# 02_connector.net
KiCad netlist of a schematic drawn in Altium Designer
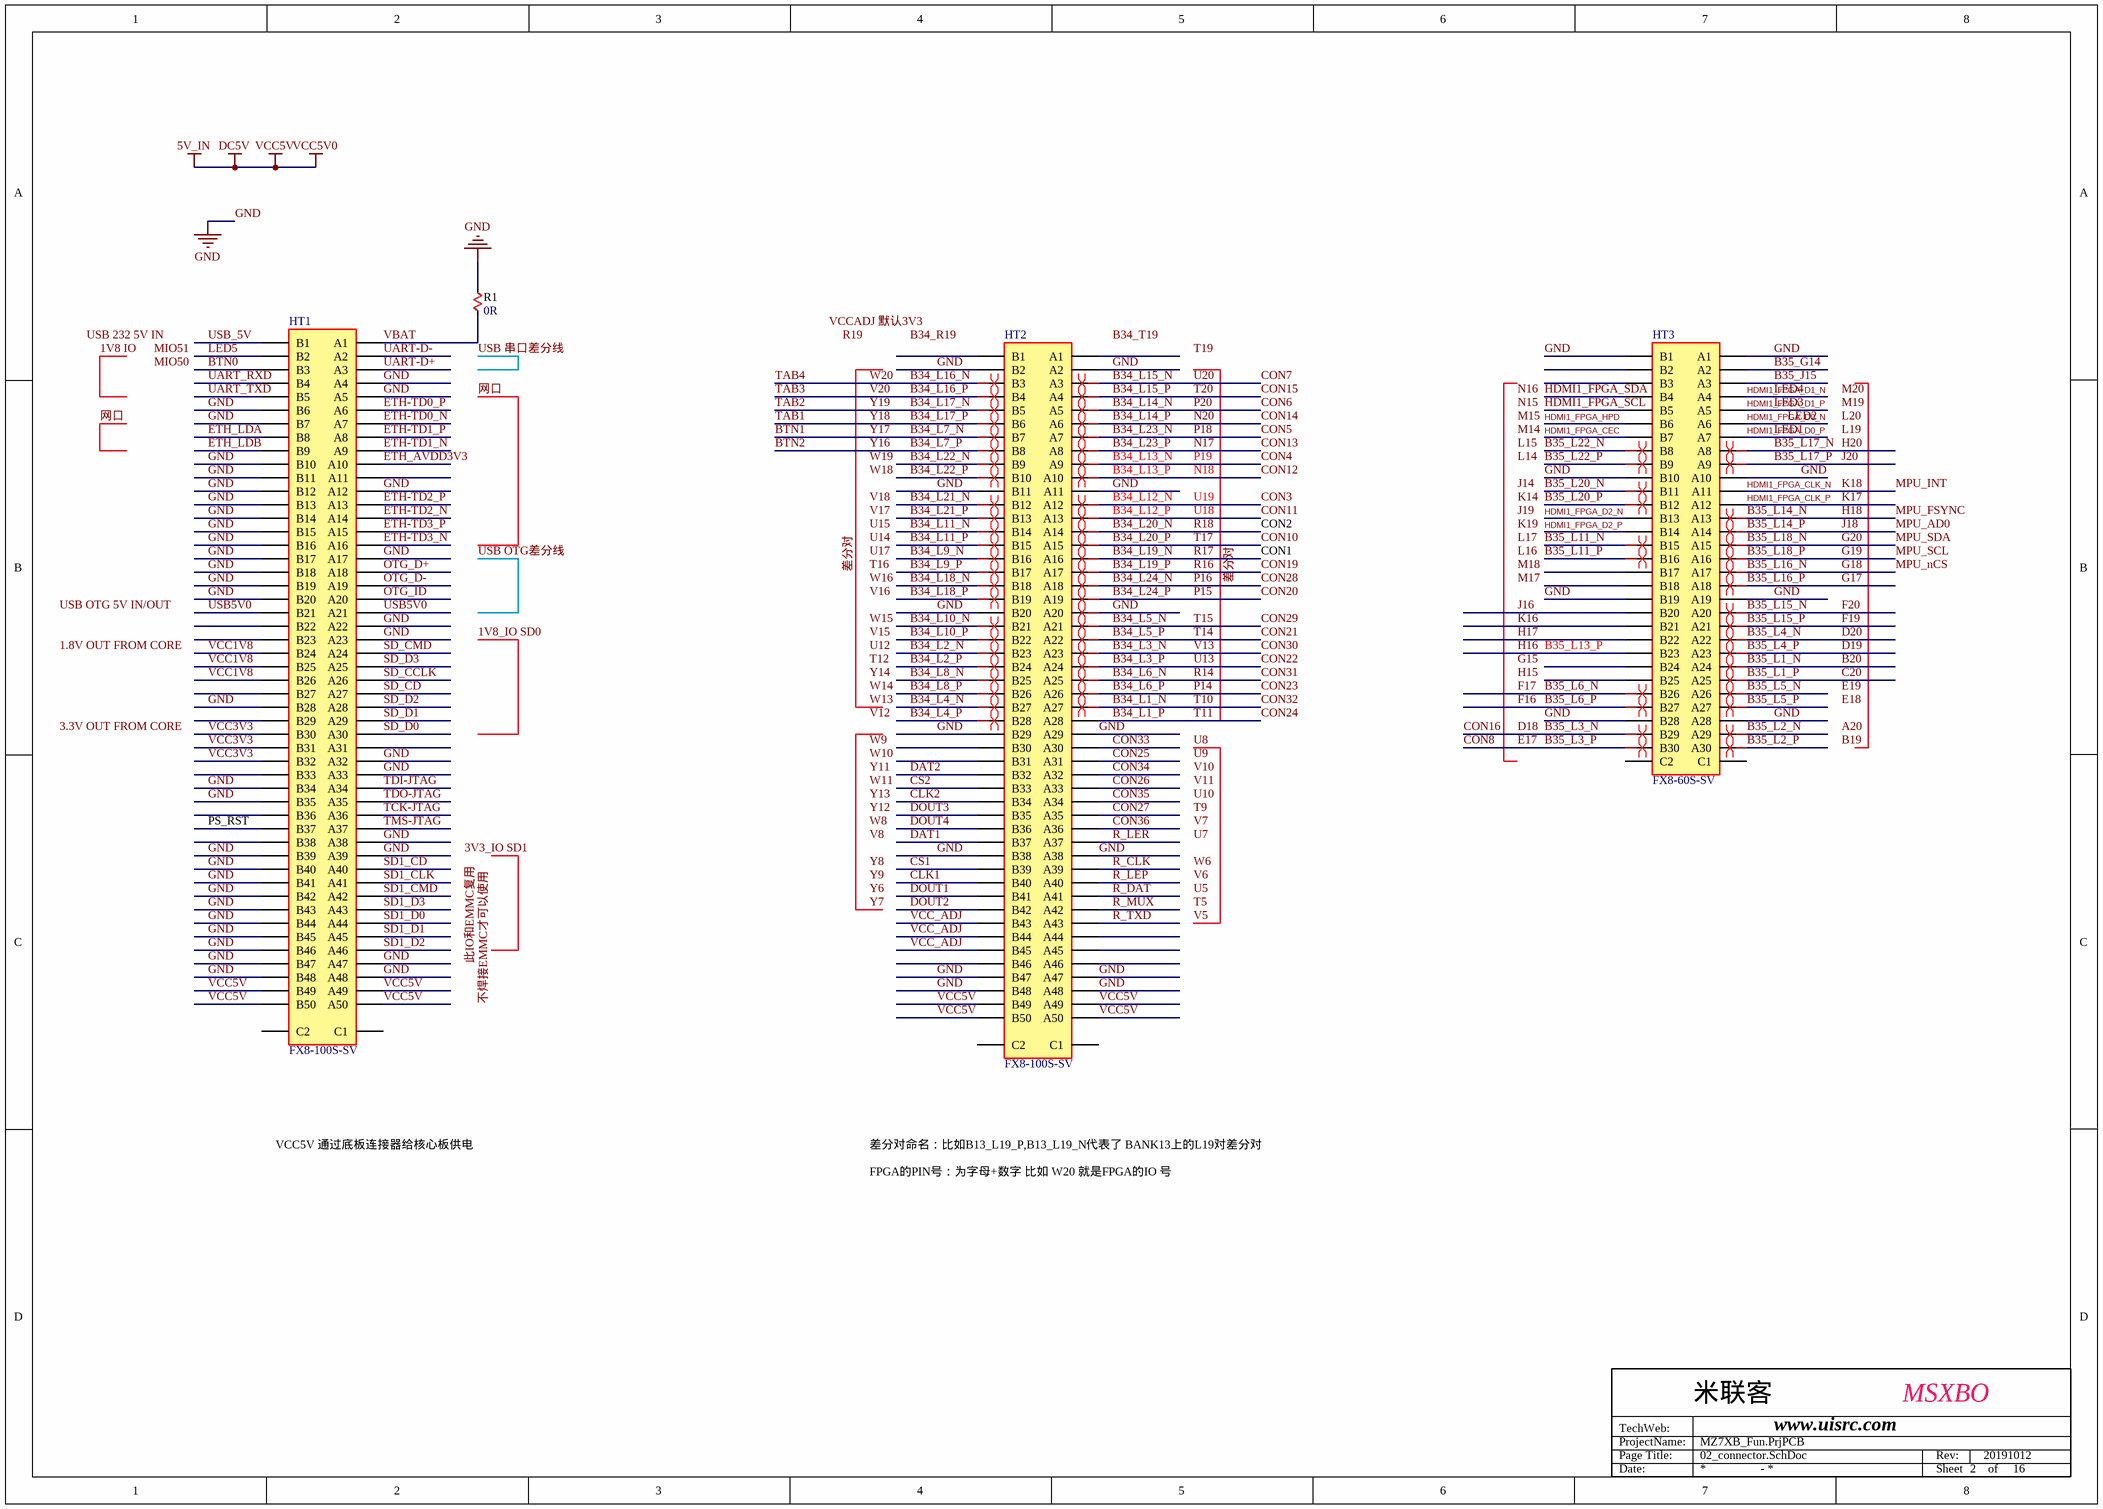
[diagram p0: 02_connector.SchDoc]

(export (version "E")
  (design (tool "Eeschema 10.0.6"))
  (components
    (comp (ref "HT1")
      (value "FX8-100S-SV")
      (footprint "FX8-100S-SV92")
      (libsource (lib "MIZ7035") (part "FX8-100P-SV92"))
    )
    (comp (ref "HT2")
      (value "FX8-100S-SV")
      (footprint "FX8-100S-SV92")
      (libsource (lib "MIZ7035") (part "FX8-100P-SV92"))
    )
    (comp (ref "HT3")
      (value "FX8-60S-SV")
      (footprint "FX8-60S-SV92")
      (libsource (lib "MiZ7010N_CORE_20161215") (part "FX8-60P-SV92"))
    )
    (comp (ref "R1")
      (value "0R")
      (footprint "R0603")
      (description "Generic Resistor")
      (libsource (lib "Digilent") (part "RESISTOR"))
    )
  )
  (nets
    (net (code "8") (name "/B20") (class "Default")
      (node (ref "HT3") (pin "A24") (pinfunction "A24_A24") (pintype "passive"))
    )
    (net (code "9") (name "/B34_L1_N") (class "Default")
      (node (ref "HT2") (pin "A27") (pinfunction "A27_A27") (pintype "passive"))
    )
    (net (code "10") (name "/B34_L1_P") (class "Default")
      (node (ref "HT2") (pin "A28") (pinfunction "A28_A28") (pintype "passive"))
    )
    (net (code "11") (name "/B34_L2_N") (class "Default")
      (node (ref "HT2") (pin "B23") (pinfunction "B23_B23") (pintype "passive"))
    )
    (net (code "12") (name "/B34_L2_P") (class "Default")
      (node (ref "HT2") (pin "B24") (pinfunction "B24_B24") (pintype "passive"))
    )
    (net (code "13") (name "/B34_L3_N") (class "Default")
      (node (ref "HT2") (pin "A23") (pinfunction "A23_A23") (pintype "passive"))
    )
    (net (code "14") (name "/B34_L3_P") (class "Default")
      (node (ref "HT2") (pin "A24") (pinfunction "A24_A24") (pintype "passive"))
    )
    (net (code "15") (name "/B34_L4_N") (class "Default")
      (node (ref "HT2") (pin "B27") (pinfunction "B27_B27") (pintype "passive"))
    )
    (net (code "16") (name "/B34_L4_P") (class "Default")
      (node (ref "HT2") (pin "B28") (pinfunction "B28_B28") (pintype "passive"))
    )
    (net (code "17") (name "/B34_L5_N") (class "Default")
      (node (ref "HT2") (pin "A21") (pinfunction "A21_A21") (pintype "passive"))
    )
    (net (code "18") (name "/B34_L5_P") (class "Default")
      (node (ref "HT2") (pin "A22") (pinfunction "A22_A22") (pintype "passive"))
    )
    (net (code "19") (name "/B34_L6_N") (class "Default")
      (node (ref "HT2") (pin "A25") (pinfunction "A25_A25") (pintype "passive"))
    )
    (net (code "20") (name "/B34_L6_P") (class "Default")
      (node (ref "HT2") (pin "A26") (pinfunction "A26_A26") (pintype "passive"))
    )
    (net (code "21") (name "/B34_L7_N") (class "Default")
      (node (ref "HT2") (pin "B7") (pinfunction "B7_B7") (pintype "passive"))
    )
    (net (code "22") (name "/B34_L7_P") (class "Default")
      (node (ref "HT2") (pin "B8") (pinfunction "B8_B8") (pintype "passive"))
    )
    (net (code "23") (name "/B34_L8_N") (class "Default")
      (node (ref "HT2") (pin "B25") (pinfunction "B25_B25") (pintype "passive"))
    )
    (net (code "24") (name "/B34_L8_P") (class "Default")
      (node (ref "HT2") (pin "B26") (pinfunction "B26_B26") (pintype "passive"))
    )
    (net (code "25") (name "/B34_L9_N") (class "Default")
      (node (ref "HT2") (pin "B16") (pinfunction "B16_B16") (pintype "passive"))
    )
    (net (code "26") (name "/B34_L9_P") (class "Default")
      (node (ref "HT2") (pin "B17") (pinfunction "B17_B17") (pintype "passive"))
    )
    (net (code "27") (name "/B34_L10_N") (class "Default")
      (node (ref "HT2") (pin "B21") (pinfunction "B21_B21") (pintype "passive"))
    )
    (net (code "28") (name "/B34_L10_P") (class "Default")
      (node (ref "HT2") (pin "B22") (pinfunction "B22_B22") (pintype "passive"))
    )
    (net (code "29") (name "/B34_L11_N") (class "Default")
      (node (ref "HT2") (pin "B14") (pinfunction "B14_B14") (pintype "passive"))
    )
    (net (code "30") (name "/B34_L11_P") (class "Default")
      (node (ref "HT2") (pin "B15") (pinfunction "B15_B15") (pintype "passive"))
    )
    (net (code "31") (name "/B34_L12_N") (class "Default")
      (node (ref "HT2") (pin "A12") (pinfunction "A12_A12") (pintype "passive"))
    )
    (net (code "32") (name "/B34_L12_P") (class "Default")
      (node (ref "HT2") (pin "A13") (pinfunction "A13_A13") (pintype "passive"))
    )
    (net (code "33") (name "/B34_L13_N") (class "Default")
      (node (ref "HT2") (pin "A9") (pinfunction "A9_A9") (pintype "passive"))
    )
    (net (code "34") (name "/B34_L13_P") (class "Default")
      (node (ref "HT2") (pin "A10") (pinfunction "A10_A10") (pintype "passive"))
    )
    (net (code "35") (name "/B34_L14_N") (class "Default")
      (node (ref "HT2") (pin "A5") (pinfunction "A5_A5") (pintype "passive"))
    )
    (net (code "36") (name "/B34_L14_P") (class "Default")
      (node (ref "HT2") (pin "A6") (pinfunction "A6_A6") (pintype "passive"))
    )
    (net (code "37") (name "/B34_L15_N") (class "Default")
      (node (ref "HT2") (pin "A3") (pinfunction "A3_A3") (pintype "passive"))
    )
    (net (code "38") (name "/B34_L15_P") (class "Default")
      (node (ref "HT2") (pin "A4") (pinfunction "A4_A4") (pintype "passive"))
    )
    (net (code "39") (name "/B34_L16_N") (class "Default")
      (node (ref "HT2") (pin "B3") (pinfunction "B3_B3") (pintype "passive"))
    )
    (net (code "40") (name "/B34_L16_P") (class "Default")
      (node (ref "HT2") (pin "B4") (pinfunction "B4_B4") (pintype "passive"))
    )
    (net (code "41") (name "/B34_L17_N") (class "Default")
      (node (ref "HT2") (pin "B5") (pinfunction "B5_B5") (pintype "passive"))
    )
    (net (code "42") (name "/B34_L17_P") (class "Default")
      (node (ref "HT2") (pin "B6") (pinfunction "B6_B6") (pintype "passive"))
    )
    (net (code "43") (name "/B34_L18_N") (class "Default")
      (node (ref "HT2") (pin "B18") (pinfunction "B18_B18") (pintype "passive"))
    )
    (net (code "44") (name "/B34_L18_P") (class "Default")
      (node (ref "HT2") (pin "B19") (pinfunction "B19_B19") (pintype "passive"))
    )
    (net (code "45") (name "/B34_L19_N") (class "Default")
      (node (ref "HT2") (pin "A16") (pinfunction "A16_A16") (pintype "passive"))
    )
    (net (code "46") (name "/B34_L19_P") (class "Default")
      (node (ref "HT2") (pin "A17") (pinfunction "A17_A17") (pintype "passive"))
    )
    (net (code "47") (name "/B34_L20_N") (class "Default")
      (node (ref "HT2") (pin "A14") (pinfunction "A14_A14") (pintype "passive"))
    )
    (net (code "48") (name "/B34_L20_P") (class "Default")
      (node (ref "HT2") (pin "A15") (pinfunction "A15_A15") (pintype "passive"))
    )
    (net (code "49") (name "/B34_L21_N") (class "Default")
      (node (ref "HT2") (pin "B12") (pinfunction "B12_B12") (pintype "passive"))
    )
    (net (code "50") (name "/B34_L21_P") (class "Default")
      (node (ref "HT2") (pin "B13") (pinfunction "B13_B13") (pintype "passive"))
    )
    (net (code "51") (name "/B34_L22_N") (class "Default")
      (node (ref "HT2") (pin "B9") (pinfunction "B9_B9") (pintype "passive"))
    )
    (net (code "52") (name "/B34_L22_P") (class "Default")
      (node (ref "HT2") (pin "B10") (pinfunction "B10_B10") (pintype "passive"))
    )
    (net (code "53") (name "/B34_L23_N") (class "Default")
      (node (ref "HT2") (pin "A7") (pinfunction "A7_A7") (pintype "passive"))
    )
    (net (code "54") (name "/B34_L23_P") (class "Default")
      (node (ref "HT2") (pin "A8") (pinfunction "A8_A8") (pintype "passive"))
    )
    (net (code "55") (name "/B34_L24_N") (class "Default")
      (node (ref "HT2") (pin "A18") (pinfunction "A18_A18") (pintype "passive"))
    )
    (net (code "56") (name "/B34_L24_P") (class "Default")
      (node (ref "HT2") (pin "A19") (pinfunction "A19_A19") (pintype "passive"))
    )
    (net (code "59") (name "/B35_G14") (class "Default")
      (node (ref "HT3") (pin "A2") (pinfunction "A2_A2") (pintype "passive"))
    )
    (net (code "60") (name "/B35_J15") (class "Default")
      (node (ref "HT3") (pin "A3") (pinfunction "A3_A3") (pintype "passive"))
    )
    (net (code "61") (name "/B35_L1_P") (class "Default")
      (node (ref "HT3") (pin "A25") (pinfunction "A25_A25") (pintype "passive"))
    )
    (net (code "62") (name "/B35_L2_N") (class "Default")
      (node (ref "HT3") (pin "A29") (pinfunction "A29_A29") (pintype "passive"))
    )
    (net (code "63") (name "/B35_L2_P") (class "Default")
      (node (ref "HT3") (pin "A30") (pinfunction "A30_A30") (pintype "passive"))
    )
    (net (code "64") (name "/B35_L3_N") (class "Default")
      (node (ref "HT3") (pin "B29") (pinfunction "B29_B29") (pintype "passive"))
    )
    (net (code "65") (name "/B35_L3_P") (class "Default")
      (node (ref "HT3") (pin "B30") (pinfunction "B30_B30") (pintype "passive"))
    )
    (net (code "66") (name "/B35_L4_N") (class "Default")
      (node (ref "HT3") (pin "A22") (pinfunction "A22_A22") (pintype "passive"))
    )
    (net (code "67") (name "/B35_L4_P") (class "Default")
      (node (ref "HT3") (pin "A23") (pinfunction "A23_A23") (pintype "passive"))
    )
    (net (code "68") (name "/B35_L5_N") (class "Default")
      (node (ref "HT3") (pin "A26") (pinfunction "A26_A26") (pintype "passive"))
    )
    (net (code "69") (name "/B35_L5_P") (class "Default")
      (node (ref "HT3") (pin "A27") (pinfunction "A27_A27") (pintype "passive"))
    )
    (net (code "70") (name "/B35_L6_N") (class "Default")
      (node (ref "HT3") (pin "B26") (pinfunction "B26_B26") (pintype "passive"))
    )
    (net (code "71") (name "/B35_L6_P") (class "Default")
      (node (ref "HT3") (pin "B27") (pinfunction "B27_B27") (pintype "passive"))
    )
    (net (code "72") (name "/B35_L11_N") (class "Default")
      (node (ref "HT3") (pin "B15") (pinfunction "B15_B15") (pintype "passive"))
    )
    (net (code "73") (name "/B35_L11_P") (class "Default")
      (node (ref "HT3") (pin "B16") (pinfunction "B16_B16") (pintype "passive"))
    )
    (net (code "74") (name "/B35_L13_P") (class "Default")
      (node (ref "HT3") (pin "B23") (pinfunction "B23_B23") (pintype "passive"))
    )
    (net (code "75") (name "/B35_L14_N") (class "Default")
      (node (ref "HT3") (pin "A13") (pinfunction "A13_A13") (pintype "passive"))
    )
    (net (code "76") (name "/B35_L14_P") (class "Default")
      (node (ref "HT3") (pin "A14") (pinfunction "A14_A14") (pintype "passive"))
    )
    (net (code "77") (name "/B35_L15_N") (class "Default")
      (node (ref "HT3") (pin "A20") (pinfunction "A20_A20") (pintype "passive"))
    )
    (net (code "78") (name "/B35_L15_P") (class "Default")
      (node (ref "HT3") (pin "A21") (pinfunction "A21_A21") (pintype "passive"))
    )
    (net (code "79") (name "/B35_L16_N") (class "Default")
      (node (ref "HT3") (pin "A17") (pinfunction "A17_A17") (pintype "passive"))
    )
    (net (code "80") (name "/B35_L16_P") (class "Default")
      (node (ref "HT3") (pin "A18") (pinfunction "A18_A18") (pintype "passive"))
    )
    (net (code "81") (name "/B35_L17_N") (class "Default")
      (node (ref "HT3") (pin "A8") (pinfunction "A8_A8") (pintype "passive"))
    )
    (net (code "82") (name "/B35_L17_P") (class "Default")
      (node (ref "HT3") (pin "A9") (pinfunction "A9_A9") (pintype "passive"))
    )
    (net (code "83") (name "/B35_L18_N") (class "Default")
      (node (ref "HT3") (pin "A15") (pinfunction "A15_A15") (pintype "passive"))
    )
    (net (code "84") (name "/B35_L18_P") (class "Default")
      (node (ref "HT3") (pin "A16") (pinfunction "A16_A16") (pintype "passive"))
    )
    (net (code "85") (name "/B35_L20_N") (class "Default")
      (node (ref "HT3") (pin "B11") (pinfunction "B11_B11") (pintype "passive"))
    )
    (net (code "86") (name "/B35_L20_P") (class "Default")
      (node (ref "HT3") (pin "B12") (pinfunction "B12_B12") (pintype "passive"))
    )
    (net (code "87") (name "/B35_L22_N") (class "Default")
      (node (ref "HT3") (pin "B8") (pinfunction "B8_B8") (pintype "passive"))
    )
    (net (code "88") (name "/B35_L22_P") (class "Default")
      (node (ref "HT3") (pin "B9") (pinfunction "B9_B9") (pintype "passive"))
    )
    (net (code "89") (name "/BTN0") (class "Default")
      (node (ref "HT1") (pin "B3") (pinfunction "B3_B3") (pintype "passive"))
    )
    (net (code "90") (name "/CLK1") (class "Default")
      (node (ref "HT2") (pin "B40") (pinfunction "B40_B40") (pintype "passive"))
    )
    (net (code "91") (name "/CLK2") (class "Default")
      (node (ref "HT2") (pin "B34") (pinfunction "B34_B34") (pintype "passive"))
    )
    (net (code "92") (name "/CON25") (class "Default")
      (node (ref "HT2") (pin "A31") (pinfunction "A31_A31") (pintype "passive"))
    )
    (net (code "93") (name "/CON26") (class "Default")
      (node (ref "HT2") (pin "A33") (pinfunction "A33_A33") (pintype "passive"))
    )
    (net (code "94") (name "/CON27") (class "Default")
      (node (ref "HT2") (pin "A35") (pinfunction "A35_A35") (pintype "passive"))
    )
    (net (code "95") (name "/CON33") (class "Default")
      (node (ref "HT2") (pin "A30") (pinfunction "A30_A30") (pintype "passive"))
    )
    (net (code "96") (name "/CON34") (class "Default")
      (node (ref "HT2") (pin "A32") (pinfunction "A32_A32") (pintype "passive"))
    )
    (net (code "97") (name "/CON35") (class "Default")
      (node (ref "HT2") (pin "A34") (pinfunction "A34_A34") (pintype "passive"))
    )
    (net (code "98") (name "/CON36") (class "Default")
      (node (ref "HT2") (pin "A36") (pinfunction "A36_A36") (pintype "passive"))
    )
    (net (code "99") (name "/CS1") (class "Default")
      (node (ref "HT2") (pin "B39") (pinfunction "B39_B39") (pintype "passive"))
    )
    (net (code "100") (name "/CS2") (class "Default")
      (node (ref "HT2") (pin "B33") (pinfunction "B33_B33") (pintype "passive"))
    )
    (net (code "101") (name "/DAT1") (class "Default")
      (node (ref "HT2") (pin "B37") (pinfunction "B37_B37") (pintype "passive"))
    )
    (net (code "102") (name "/DAT2") (class "Default")
      (node (ref "HT2") (pin "B32") (pinfunction "B32_B32") (pintype "passive"))
    )
    (net (code "103") (name "/DOUT1") (class "Default")
      (node (ref "HT2") (pin "B41") (pinfunction "B41_B41") (pintype "passive"))
    )
    (net (code "104") (name "/DOUT2") (class "Default")
      (node (ref "HT2") (pin "B42") (pinfunction "B42_B42") (pintype "passive"))
    )
    (net (code "105") (name "/DOUT3") (class "Default")
      (node (ref "HT2") (pin "B35") (pinfunction "B35_B35") (pintype "passive"))
    )
    (net (code "106") (name "/DOUT4") (class "Default")
      (node (ref "HT2") (pin "B36") (pinfunction "B36_B36") (pintype "passive"))
    )
    (net (code "109") (name "/ETH-TD0_N") (class "Default")
      (node (ref "HT1") (pin "A7") (pinfunction "A7_A7") (pintype "passive"))
    )
    (net (code "110") (name "/ETH-TD0_P") (class "Default")
      (node (ref "HT1") (pin "A6") (pinfunction "A6_A6") (pintype "passive"))
    )
    (net (code "111") (name "/ETH-TD1_N") (class "Default")
      (node (ref "HT1") (pin "A9") (pinfunction "A9_A9") (pintype "passive"))
    )
    (net (code "112") (name "/ETH-TD1_P") (class "Default")
      (node (ref "HT1") (pin "A8") (pinfunction "A8_A8") (pintype "passive"))
    )
    (net (code "113") (name "/ETH-TD2_N") (class "Default")
      (node (ref "HT1") (pin "A14") (pinfunction "A14_A14") (pintype "passive"))
    )
    (net (code "114") (name "/ETH-TD2_P") (class "Default")
      (node (ref "HT1") (pin "A13") (pinfunction "A13_A13") (pintype "passive"))
    )
    (net (code "115") (name "/ETH-TD3_N") (class "Default")
      (node (ref "HT1") (pin "A16") (pinfunction "A16_A16") (pintype "passive"))
    )
    (net (code "116") (name "/ETH-TD3_P") (class "Default")
      (node (ref "HT1") (pin "A15") (pinfunction "A15_A15") (pintype "passive"))
    )
    (net (code "117") (name "/ETH_AVDD3V3") (class "Default")
      (node (ref "HT1") (pin "A10") (pinfunction "A10_A10") (pintype "passive"))
    )
    (net (code "118") (name "/ETH_LDA") (class "Default")
      (node (ref "HT1") (pin "B8") (pinfunction "B8_B8") (pintype "passive"))
    )
    (net (code "119") (name "/ETH_LDB") (class "Default")
      (node (ref "HT1") (pin "B9") (pinfunction "B9_B9") (pintype "passive"))
    )
    (net (code "122") (name "/H17") (class "Default")
      (node (ref "HT3") (pin "B22") (pinfunction "B22_B22") (pintype "passive"))
    )
    (net (code "123") (name "/HDMI1_FPGA_CEC") (class "Default")
      (node (ref "HT3") (pin "B7") (pinfunction "B7_B7") (pintype "passive"))
    )
    (net (code "124") (name "/HDMI1_FPGA_CLK_N") (class "Default")
      (node (ref "HT3") (pin "A11") (pinfunction "A11_A11") (pintype "passive"))
    )
    (net (code "125") (name "/HDMI1_FPGA_CLK_P") (class "Default")
      (node (ref "HT3") (pin "A12") (pinfunction "A12_A12") (pintype "passive"))
    )
    (net (code "126") (name "/HDMI1_FPGA_D0_N") (class "Default")
      (node (ref "HT3") (pin "A6") (pinfunction "A6_A6") (pintype "passive"))
    )
    (net (code "127") (name "/HDMI1_FPGA_D0_P") (class "Default")
      (node (ref "HT3") (pin "A7") (pinfunction "A7_A7") (pintype "passive"))
    )
    (net (code "128") (name "/HDMI1_FPGA_D1_N") (class "Default")
      (node (ref "HT3") (pin "A4") (pinfunction "A4_A4") (pintype "passive"))
    )
    (net (code "129") (name "/HDMI1_FPGA_D1_P") (class "Default")
      (node (ref "HT3") (pin "A5") (pinfunction "A5_A5") (pintype "passive"))
    )
    (net (code "130") (name "/HDMI1_FPGA_D2_N") (class "Default")
      (node (ref "HT3") (pin "B13") (pinfunction "B13_B13") (pintype "passive"))
    )
    (net (code "131") (name "/HDMI1_FPGA_D2_P") (class "Default")
      (node (ref "HT3") (pin "B14") (pinfunction "B14_B14") (pintype "passive"))
    )
    (net (code "132") (name "/HDMI1_FPGA_HPD") (class "Default")
      (node (ref "HT3") (pin "B6") (pinfunction "B6_B6") (pintype "passive"))
    )
    (net (code "133") (name "/HDMI1_FPGA_SCL") (class "Default")
      (node (ref "HT3") (pin "B5") (pinfunction "B5_B5") (pintype "passive"))
    )
    (net (code "134") (name "/HDMI1_FPGA_SDA") (class "Default")
      (node (ref "HT3") (pin "B4") (pinfunction "B4_B4") (pintype "passive"))
    )
    (net (code "136") (name "/J16") (class "Default")
      (node (ref "HT3") (pin "B20") (pinfunction "B20_B20") (pintype "passive"))
    )
    (net (code "139") (name "/K16") (class "Default")
      (node (ref "HT3") (pin "B21") (pinfunction "B21_B21") (pintype "passive"))
    )
    (net (code "147") (name "/LED5") (class "Default")
      (node (ref "HT1") (pin "B2") (pinfunction "B2_B2") (pintype "passive"))
    )
    (net (code "158") (name "/OTG_D+") (class "Default")
      (node (ref "HT1") (pin "A18") (pinfunction "A18_A18") (pintype "passive"))
    )
    (net (code "159") (name "/OTG_D-") (class "Default")
      (node (ref "HT1") (pin "A19") (pinfunction "A19_A19") (pintype "passive"))
    )
    (net (code "160") (name "/OTG_ID") (class "Default")
      (node (ref "HT1") (pin "A20") (pinfunction "A20_A20") (pintype "passive"))
    )
    (net (code "161") (name "/PS_RST") (class "Default")
      (node (ref "HT1") (pin "B37") (pinfunction "B37_B37") (pintype "passive"))
    )
    (net (code "163") (name "/R_CLK") (class "Default")
      (node (ref "HT2") (pin "A39") (pinfunction "A39_A39") (pintype "passive"))
    )
    (net (code "164") (name "/R_DAT") (class "Default")
      (node (ref "HT2") (pin "A41") (pinfunction "A41_A41") (pintype "passive"))
    )
    (net (code "165") (name "/R_LEP") (class "Default")
      (node (ref "HT2") (pin "A40") (pinfunction "A40_A40") (pintype "passive"))
    )
    (net (code "166") (name "/R_LER") (class "Default")
      (node (ref "HT2") (pin "A37") (pinfunction "A37_A37") (pintype "passive"))
    )
    (net (code "167") (name "/R_MUX") (class "Default")
      (node (ref "HT2") (pin "A42") (pinfunction "A42_A42") (pintype "passive"))
    )
    (net (code "168") (name "/R_TXD") (class "Default")
      (node (ref "HT2") (pin "A43") (pinfunction "A43_A43") (pintype "passive"))
    )
    (net (code "169") (name "/SD1_CD") (class "Default")
      (node (ref "HT1") (pin "A40") (pinfunction "A40_A40") (pintype "passive"))
    )
    (net (code "170") (name "/SD1_CLK") (class "Default")
      (node (ref "HT1") (pin "A41") (pinfunction "A41_A41") (pintype "passive"))
    )
    (net (code "171") (name "/SD1_CMD") (class "Default")
      (node (ref "HT1") (pin "A42") (pinfunction "A42_A42") (pintype "passive"))
    )
    (net (code "172") (name "/SD1_D0") (class "Default")
      (node (ref "HT1") (pin "A44") (pinfunction "A44_A44") (pintype "passive"))
    )
    (net (code "173") (name "/SD1_D1") (class "Default")
      (node (ref "HT1") (pin "A45") (pinfunction "A45_A45") (pintype "passive"))
    )
    (net (code "174") (name "/SD1_D2") (class "Default")
      (node (ref "HT1") (pin "A46") (pinfunction "A46_A46") (pintype "passive"))
    )
    (net (code "175") (name "/SD1_D3") (class "Default")
      (node (ref "HT1") (pin "A43") (pinfunction "A43_A43") (pintype "passive"))
    )
    (net (code "176") (name "/SD_CCLK") (class "Default")
      (node (ref "HT1") (pin "A26") (pinfunction "A26_A26") (pintype "passive"))
    )
    (net (code "177") (name "/SD_CD") (class "Default")
      (node (ref "HT1") (pin "A27") (pinfunction "A27_A27") (pintype "passive"))
    )
    (net (code "178") (name "/SD_CMD") (class "Default")
      (node (ref "HT1") (pin "A24") (pinfunction "A24_A24") (pintype "passive"))
    )
    (net (code "179") (name "/SD_D0") (class "Default")
      (node (ref "HT1") (pin "A30") (pinfunction "A30_A30") (pintype "passive"))
    )
    (net (code "180") (name "/SD_D1") (class "Default")
      (node (ref "HT1") (pin "A29") (pinfunction "A29_A29") (pintype "passive"))
    )
    (net (code "181") (name "/SD_D2") (class "Default")
      (node (ref "HT1") (pin "A28") (pinfunction "A28_A28") (pintype "passive"))
    )
    (net (code "182") (name "/SD_D3") (class "Default")
      (node (ref "HT1") (pin "A25") (pinfunction "A25_A25") (pintype "passive"))
    )
    (net (code "188") (name "/TCK-JTAG") (class "Default")
      (node (ref "HT1") (pin "A36") (pinfunction "A36_A36") (pintype "passive"))
    )
    (net (code "189") (name "/TDI-JTAG") (class "Default")
      (node (ref "HT1") (pin "A34") (pinfunction "A34_A34") (pintype "passive"))
    )
    (net (code "190") (name "/TDO-JTAG") (class "Default")
      (node (ref "HT1") (pin "A35") (pinfunction "A35_A35") (pintype "passive"))
    )
    (net (code "191") (name "/TMS-JTAG") (class "Default")
      (node (ref "HT1") (pin "A37") (pinfunction "A37_A37") (pintype "passive"))
    )
    (net (code "201") (name "/UART-D+") (class "Default")
      (node (ref "HT1") (pin "A3") (pinfunction "A3_A3") (pintype "passive"))
    )
    (net (code "202") (name "/UART-D-") (class "Default")
      (node (ref "HT1") (pin "A2") (pinfunction "A2_A2") (pintype "passive"))
    )
    (net (code "203") (name "/UART_RXD") (class "Default")
      (node (ref "HT1") (pin "B4") (pinfunction "B4_B4") (pintype "passive"))
    )
    (net (code "204") (name "/UART_TXD") (class "Default")
      (node (ref "HT1") (pin "B5") (pinfunction "B5_B5") (pintype "passive"))
    )
    (net (code "209") (name "/USB5V0") (class "Default")
      (node (ref "HT1") (pin "A21") (pinfunction "A21_A21") (pintype "passive"))
      (node (ref "HT1") (pin "B21") (pinfunction "B21_B21") (pintype "passive"))
    )
    (net (code "210") (name "/USB_5V") (class "Default")
      (node (ref "HT1") (pin "B1") (pinfunction "B1_B1") (pintype "passive"))
    )
    (net (code "222") (name "/VBAT") (class "Default")
      (node (ref "HT1") (pin "A1") (pinfunction "A1_A1") (pintype "passive"))
      (node (ref "R1") (pin "2") (pinfunction "2_2") (pintype "passive"))
    )
    (net (code "223") (name "/VCC1V8") (class "Default")
      (node (ref "HT1") (pin "B24") (pinfunction "B24_B24") (pintype "passive"))
      (node (ref "HT1") (pin "B25") (pinfunction "B25_B25") (pintype "passive"))
      (node (ref "HT1") (pin "B26") (pinfunction "B26_B26") (pintype "passive"))
    )
    (net (code "224") (name "/VCC3V3") (class "Default")
      (node (ref "HT1") (pin "B30") (pinfunction "B30_B30") (pintype "passive"))
      (node (ref "HT1") (pin "B31") (pinfunction "B31_B31") (pintype "passive"))
      (node (ref "HT1") (pin "B32") (pinfunction "B32_B32") (pintype "passive"))
    )
    (net (code "226") (name "/VCC_ADJ") (class "Default")
      (node (ref "HT2") (pin "B43") (pinfunction "B43_B43") (pintype "passive"))
      (node (ref "HT2") (pin "B44") (pinfunction "B44_B44") (pintype "passive"))
      (node (ref "HT2") (pin "B45") (pinfunction "B45_B45") (pintype "passive"))
    )
    (net (code "249") (name "5V_IN") (class "Default")
      (node (ref "HT1") (pin "A49") (pinfunction "A49_A49") (pintype "passive"))
      (node (ref "HT1") (pin "A50") (pinfunction "A50_A50") (pintype "passive"))
      (node (ref "HT1") (pin "B49") (pinfunction "B49_B49") (pintype "passive"))
      (node (ref "HT1") (pin "B50") (pinfunction "B50_B50") (pintype "passive"))
      (node (ref "HT2") (pin "A49") (pinfunction "A49_A49") (pintype "passive"))
      (node (ref "HT2") (pin "A50") (pinfunction "A50_A50") (pintype "passive"))
      (node (ref "HT2") (pin "B49") (pinfunction "B49_B49") (pintype "passive"))
      (node (ref "HT2") (pin "B50") (pinfunction "B50_B50") (pintype "passive"))
    )
    (net (code "250") (name "GND") (class "Default")
      (node (ref "HT1") (pin "A12") (pinfunction "A12_A12") (pintype "passive"))
      (node (ref "HT1") (pin "A17") (pinfunction "A17_A17") (pintype "passive"))
      (node (ref "HT1") (pin "A22") (pinfunction "A22_A22") (pintype "passive"))
      (node (ref "HT1") (pin "A23") (pinfunction "A23_A23") (pintype "passive"))
      (node (ref "HT1") (pin "A32") (pinfunction "A32_A32") (pintype "passive"))
      (node (ref "HT1") (pin "A33") (pinfunction "A33_A33") (pintype "passive"))
      (node (ref "HT1") (pin "A38") (pinfunction "A38_A38") (pintype "passive"))
      (node (ref "HT1") (pin "A39") (pinfunction "A39_A39") (pintype "passive"))
      (node (ref "HT1") (pin "A4") (pinfunction "A4_A4") (pintype "passive"))
      (node (ref "HT1") (pin "A47") (pinfunction "A47_A47") (pintype "passive"))
      (node (ref "HT1") (pin "A48") (pinfunction "A48_A48") (pintype "passive"))
      (node (ref "HT1") (pin "A5") (pinfunction "A5_A5") (pintype "passive"))
      (node (ref "HT1") (pin "B10") (pinfunction "B10_B10") (pintype "passive"))
      (node (ref "HT1") (pin "B11") (pinfunction "B11_B11") (pintype "passive"))
      (node (ref "HT1") (pin "B12") (pinfunction "B12_B12") (pintype "passive"))
      (node (ref "HT1") (pin "B13") (pinfunction "B13_B13") (pintype "passive"))
      (node (ref "HT1") (pin "B14") (pinfunction "B14_B14") (pintype "passive"))
      (node (ref "HT1") (pin "B15") (pinfunction "B15_B15") (pintype "passive"))
      (node (ref "HT1") (pin "B16") (pinfunction "B16_B16") (pintype "passive"))
      (node (ref "HT1") (pin "B17") (pinfunction "B17_B17") (pintype "passive"))
      (node (ref "HT1") (pin "B18") (pinfunction "B18_B18") (pintype "passive"))
      (node (ref "HT1") (pin "B19") (pinfunction "B19_B19") (pintype "passive"))
      (node (ref "HT1") (pin "B20") (pinfunction "B20_B20") (pintype "passive"))
      (node (ref "HT1") (pin "B28") (pinfunction "B28_B28") (pintype "passive"))
      (node (ref "HT1") (pin "B34") (pinfunction "B34_B34") (pintype "passive"))
      (node (ref "HT1") (pin "B35") (pinfunction "B35_B35") (pintype "passive"))
      (node (ref "HT1") (pin "B39") (pinfunction "B39_B39") (pintype "passive"))
      (node (ref "HT1") (pin "B40") (pinfunction "B40_B40") (pintype "passive"))
      (node (ref "HT1") (pin "B41") (pinfunction "B41_B41") (pintype "passive"))
      (node (ref "HT1") (pin "B42") (pinfunction "B42_B42") (pintype "passive"))
      (node (ref "HT1") (pin "B43") (pinfunction "B43_B43") (pintype "passive"))
      (node (ref "HT1") (pin "B44") (pinfunction "B44_B44") (pintype "passive"))
      (node (ref "HT1") (pin "B45") (pinfunction "B45_B45") (pintype "passive"))
      (node (ref "HT1") (pin "B46") (pinfunction "B46_B46") (pintype "passive"))
      (node (ref "HT1") (pin "B47") (pinfunction "B47_B47") (pintype "passive"))
      (node (ref "HT1") (pin "B48") (pinfunction "B48_B48") (pintype "passive"))
      (node (ref "HT1") (pin "B6") (pinfunction "B6_B6") (pintype "passive"))
      (node (ref "HT1") (pin "B7") (pinfunction "B7_B7") (pintype "passive"))
      (node (ref "HT2") (pin "A11") (pinfunction "A11_A11") (pintype "passive"))
      (node (ref "HT2") (pin "A2") (pinfunction "A2_A2") (pintype "passive"))
      (node (ref "HT2") (pin "A20") (pinfunction "A20_A20") (pintype "passive"))
      (node (ref "HT2") (pin "A29") (pinfunction "A29_A29") (pintype "passive"))
      (node (ref "HT2") (pin "A38") (pinfunction "A38_A38") (pintype "passive"))
      (node (ref "HT2") (pin "A47") (pinfunction "A47_A47") (pintype "passive"))
      (node (ref "HT2") (pin "A48") (pinfunction "A48_A48") (pintype "passive"))
      (node (ref "HT2") (pin "B11") (pinfunction "B11_B11") (pintype "passive"))
      (node (ref "HT2") (pin "B2") (pinfunction "B2_B2") (pintype "passive"))
      (node (ref "HT2") (pin "B20") (pinfunction "B20_B20") (pintype "passive"))
      (node (ref "HT2") (pin "B29") (pinfunction "B29_B29") (pintype "passive"))
      (node (ref "HT2") (pin "B38") (pinfunction "B38_B38") (pintype "passive"))
      (node (ref "HT2") (pin "B47") (pinfunction "B47_B47") (pintype "passive"))
      (node (ref "HT2") (pin "B48") (pinfunction "B48_B48") (pintype "passive"))
      (node (ref "HT3") (pin "A1") (pinfunction "A1_A1") (pintype "passive"))
      (node (ref "HT3") (pin "A10") (pinfunction "A10_A10") (pintype "passive"))
      (node (ref "HT3") (pin "A19") (pinfunction "A19_A19") (pintype "passive"))
      (node (ref "HT3") (pin "A28") (pinfunction "A28_A28") (pintype "passive"))
      (node (ref "HT3") (pin "B1") (pinfunction "B1_B1") (pintype "passive"))
      (node (ref "HT3") (pin "B10") (pinfunction "B10_B10") (pintype "passive"))
      (node (ref "HT3") (pin "B19") (pinfunction "B19_B19") (pintype "passive"))
      (node (ref "HT3") (pin "B28") (pinfunction "B28_B28") (pintype "passive"))
      (node (ref "R1") (pin "1") (pinfunction "1_1") (pintype "passive"))
    )
    (net (code "251") (name "unconnected-(HT1-PadA11)") (class "Default")
      (node (ref "HT1") (pin "A11") (pinfunction "A11_A11") (pintype "passive"))
    )
    (net (code "252") (name "unconnected-(HT1-PadA31)") (class "Default")
      (node (ref "HT1") (pin "A31") (pinfunction "A31_A31") (pintype "passive"))
    )
    (net (code "253") (name "unconnected-(HT1-PadB22)") (class "Default")
      (node (ref "HT1") (pin "B22") (pinfunction "B22_B22") (pintype "passive"))
    )
    (net (code "254") (name "unconnected-(HT1-PadB23)") (class "Default")
      (node (ref "HT1") (pin "B23") (pinfunction "B23_B23") (pintype "passive"))
    )
    (net (code "255") (name "unconnected-(HT1-PadB27)") (class "Default")
      (node (ref "HT1") (pin "B27") (pinfunction "B27_B27") (pintype "passive"))
    )
    (net (code "256") (name "unconnected-(HT1-PadB29)") (class "Default")
      (node (ref "HT1") (pin "B29") (pinfunction "B29_B29") (pintype "passive"))
    )
    (net (code "257") (name "unconnected-(HT1-PadB33)") (class "Default")
      (node (ref "HT1") (pin "B33") (pinfunction "B33_B33") (pintype "passive"))
    )
    (net (code "258") (name "unconnected-(HT1-PadB36)") (class "Default")
      (node (ref "HT1") (pin "B36") (pinfunction "B36_B36") (pintype "passive"))
    )
    (net (code "259") (name "unconnected-(HT1-PadB38)") (class "Default")
      (node (ref "HT1") (pin "B38") (pinfunction "B38_B38") (pintype "passive"))
    )
    (net (code "260") (name "unconnected-(HT1-PadC1)") (class "Default")
      (node (ref "HT1") (pin "C1") (pinfunction "C1_C1") (pintype "passive"))
    )
    (net (code "261") (name "unconnected-(HT1-PadC2)") (class "Default")
      (node (ref "HT1") (pin "C2") (pinfunction "C2_C2") (pintype "passive"))
    )
    (net (code "262") (name "unconnected-(HT2-PadA1)") (class "Default")
      (node (ref "HT2") (pin "A1") (pinfunction "A1_A1") (pintype "passive"))
    )
    (net (code "263") (name "unconnected-(HT2-PadA44)") (class "Default")
      (node (ref "HT2") (pin "A44") (pinfunction "A44_A44") (pintype "passive"))
    )
    (net (code "264") (name "unconnected-(HT2-PadA45)") (class "Default")
      (node (ref "HT2") (pin "A45") (pinfunction "A45_A45") (pintype "passive"))
    )
    (net (code "265") (name "unconnected-(HT2-PadA46)") (class "Default")
      (node (ref "HT2") (pin "A46") (pinfunction "A46_A46") (pintype "passive"))
    )
    (net (code "266") (name "unconnected-(HT2-PadB1)") (class "Default")
      (node (ref "HT2") (pin "B1") (pinfunction "B1_B1") (pintype "passive"))
    )
    (net (code "267") (name "unconnected-(HT2-PadB30)") (class "Default")
      (node (ref "HT2") (pin "B30") (pinfunction "B30_B30") (pintype "passive"))
    )
    (net (code "268") (name "unconnected-(HT2-PadB31)") (class "Default")
      (node (ref "HT2") (pin "B31") (pinfunction "B31_B31") (pintype "passive"))
    )
    (net (code "269") (name "unconnected-(HT2-PadB46)") (class "Default")
      (node (ref "HT2") (pin "B46") (pinfunction "B46_B46") (pintype "passive"))
    )
    (net (code "270") (name "unconnected-(HT2-PadC1)") (class "Default")
      (node (ref "HT2") (pin "C1") (pinfunction "C1_C1") (pintype "passive"))
    )
    (net (code "271") (name "unconnected-(HT2-PadC2)") (class "Default")
      (node (ref "HT2") (pin "C2") (pinfunction "C2_C2") (pintype "passive"))
    )
    (net (code "272") (name "unconnected-(HT3-PadB2)") (class "Default")
      (node (ref "HT3") (pin "B2") (pinfunction "B2_B2") (pintype "passive"))
    )
    (net (code "273") (name "unconnected-(HT3-PadB3)") (class "Default")
      (node (ref "HT3") (pin "B3") (pinfunction "B3_B3") (pintype "passive"))
    )
    (net (code "274") (name "unconnected-(HT3-PadB17)") (class "Default")
      (node (ref "HT3") (pin "B17") (pinfunction "B17_B17") (pintype "passive"))
    )
    (net (code "275") (name "unconnected-(HT3-PadB18)") (class "Default")
      (node (ref "HT3") (pin "B18") (pinfunction "B18_B18") (pintype "passive"))
    )
    (net (code "276") (name "unconnected-(HT3-PadB24)") (class "Default")
      (node (ref "HT3") (pin "B24") (pinfunction "B24_B24") (pintype "passive"))
    )
    (net (code "277") (name "unconnected-(HT3-PadB25)") (class "Default")
      (node (ref "HT3") (pin "B25") (pinfunction "B25_B25") (pintype "passive"))
    )
    (net (code "278") (name "unconnected-(HT3-PadC1)") (class "Default")
      (node (ref "HT3") (pin "C1") (pinfunction "C1_C1") (pintype "passive"))
    )
    (net (code "279") (name "unconnected-(HT3-PadC2)") (class "Default")
      (node (ref "HT3") (pin "C2") (pinfunction "C2_C2") (pintype "passive"))
    )
  )
)
